# nano_bt_langsung.net
KiCad netlist of a schematic drawn in EAGLE
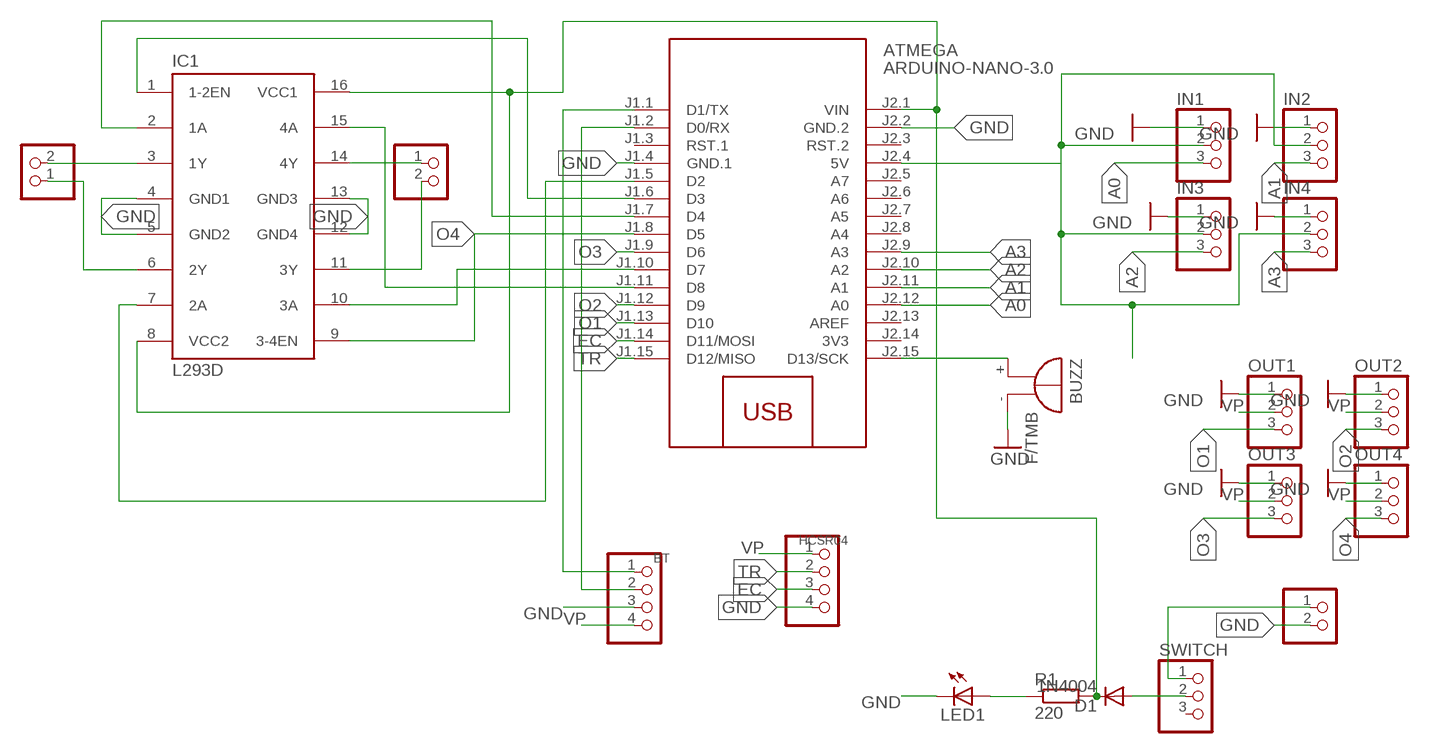
[diagram p0: schematic, sheet 1]

(export (version "E")
  (design (tool "Eeschema 10.0.6"))
  (components
    (comp (ref "ATMEGA")
      (value "ARDUINO-NANO-3.0")
      (footprint "eagle-import:ARDUINO-NANO-3.0")
      (libsource (lib "eagle-import") (part "ARDUINO-NANO-3.0"))
    )
    (comp (ref "BT")
      (value "PINHD-1X4")
      (footprint "eagle-import:1X04")
      (libsource (lib "eagle-import") (part "PINHD-1X4"))
    )
    (comp (ref "BUZZ")
      (value "F/TMB")
      (footprint "eagle-import:F_TMB")
      (libsource (lib "eagle-import") (part "F/TMB"))
    )
    (comp (ref "D1")
      (value "1N4004")
      (footprint "eagle-import:DO41-10")
      (libsource (lib "eagle-import") (part "1N4004"))
    )
    (comp (ref "DCV")
      (value "PINHD-1X2")
      (footprint "eagle-import:1X02")
      (libsource (lib "eagle-import") (part "PINHD-1X2"))
    )
    (comp (ref "HCSR04")
      (value "PINHD-1X4")
      (footprint "eagle-import:1X04")
      (libsource (lib "eagle-import") (part "PINHD-1X4"))
    )
    (comp (ref "IC1")
      (value "L293D")
      (footprint "eagle-import:DIL16")
      (libsource (lib "eagle-import") (part "L293D"))
    )
    (comp (ref "IN1")
      (value "PINHD-1X3")
      (footprint "eagle-import:1X03")
      (libsource (lib "eagle-import") (part "PINHD-1X3"))
    )
    (comp (ref "IN2")
      (value "PINHD-1X3")
      (footprint "eagle-import:1X03")
      (libsource (lib "eagle-import") (part "PINHD-1X3"))
    )
    (comp (ref "IN3")
      (value "PINHD-1X3")
      (footprint "eagle-import:1X03")
      (libsource (lib "eagle-import") (part "PINHD-1X3"))
    )
    (comp (ref "IN4")
      (value "PINHD-1X3")
      (footprint "eagle-import:1X03")
      (libsource (lib "eagle-import") (part "PINHD-1X3"))
    )
    (comp (ref "LED1")
      (value "LED3MM")
      (footprint "eagle-import:LED3MM")
      (libsource (lib "eagle-import") (part "LED3MM"))
    )
    (comp (ref "MT1")
      (value "PINHD-1X2")
      (footprint "eagle-import:1X02")
      (libsource (lib "eagle-import") (part "PINHD-1X2"))
    )
    (comp (ref "MT2")
      (value "PINHD-1X2")
      (footprint "eagle-import:1X02")
      (libsource (lib "eagle-import") (part "PINHD-1X2"))
    )
    (comp (ref "OUT1")
      (value "PINHD-1X3")
      (footprint "eagle-import:1X03")
      (libsource (lib "eagle-import") (part "PINHD-1X3"))
    )
    (comp (ref "OUT2")
      (value "PINHD-1X3")
      (footprint "eagle-import:1X03")
      (libsource (lib "eagle-import") (part "PINHD-1X3"))
    )
    (comp (ref "OUT3")
      (value "PINHD-1X3")
      (footprint "eagle-import:1X03")
      (libsource (lib "eagle-import") (part "PINHD-1X3"))
    )
    (comp (ref "OUT4")
      (value "PINHD-1X3")
      (footprint "eagle-import:1X03")
      (libsource (lib "eagle-import") (part "PINHD-1X3"))
    )
    (comp (ref "R1")
      (value "220")
      (footprint "eagle-import:0204_7")
      (libsource (lib "eagle-import") (part "R-EU_0204/7"))
    )
    (comp (ref "SWITCH")
      (value "PINHD-1X3")
      (footprint "eagle-import:1X03")
      (libsource (lib "eagle-import") (part "adafruit_arduino_PINHD-1X3"))
    )
  )
  (nets
    (net (code "1") (name "/3V3") (class "Default")
      (node (ref "ATMEGA") (pin "J2.14") (pinfunction "3V3_J2.14") (pintype "power_in"))
    )
    (net (code "2") (name "/VP") (class "Default")
      (node (ref "ATMEGA") (pin "J2.4") (pinfunction "5V_J2.4") (pintype "power_in"))
      (node (ref "BT") (pin "4") (pinfunction "4_4") (pintype "passive"))
      (node (ref "HCSR04") (pin "1") (pinfunction "1_1") (pintype "passive"))
      (node (ref "IN1") (pin "2") (pinfunction "2_2") (pintype "passive"))
      (node (ref "IN2") (pin "2") (pinfunction "2_2") (pintype "passive"))
      (node (ref "IN3") (pin "2") (pinfunction "2_2") (pintype "passive"))
      (node (ref "IN4") (pin "2") (pinfunction "2_2") (pintype "passive"))
      (node (ref "OUT1") (pin "2") (pinfunction "2_2") (pintype "passive"))
      (node (ref "OUT2") (pin "2") (pinfunction "2_2") (pintype "passive"))
      (node (ref "OUT3") (pin "2") (pinfunction "2_2") (pintype "passive"))
      (node (ref "OUT4") (pin "2") (pinfunction "2_2") (pintype "passive"))
    )
    (net (code "3") (name "A0") (class "Default")
      (node (ref "ATMEGA") (pin "J2.12") (pinfunction "A0_J2.12") (pintype "bidirectional"))
      (node (ref "IN1") (pin "3") (pinfunction "3_3") (pintype "passive"))
    )
    (net (code "4") (name "A1") (class "Default")
      (node (ref "ATMEGA") (pin "J2.11") (pinfunction "A1_J2.11") (pintype "bidirectional"))
      (node (ref "IN2") (pin "3") (pinfunction "3_3") (pintype "passive"))
    )
    (net (code "5") (name "A2") (class "Default")
      (node (ref "ATMEGA") (pin "J2.10") (pinfunction "A2_J2.10") (pintype "bidirectional"))
      (node (ref "IN3") (pin "3") (pinfunction "3_3") (pintype "passive"))
    )
    (net (code "6") (name "A3") (class "Default")
      (node (ref "ATMEGA") (pin "J2.9") (pinfunction "A3_J2.9") (pintype "bidirectional"))
      (node (ref "IN4") (pin "3") (pinfunction "3_3") (pintype "passive"))
    )
    (net (code "7") (name "EC") (class "Default")
      (node (ref "ATMEGA") (pin "J1.14") (pinfunction "D11/MOSI_J1.14") (pintype "bidirectional"))
      (node (ref "HCSR04") (pin "3") (pinfunction "3_3") (pintype "passive"))
    )
    (net (code "8") (name "GND") (class "Default")
      (node (ref "ATMEGA") (pin "J1.4") (pinfunction "GND.1_J1.4") (pintype "power_in"))
      (node (ref "ATMEGA") (pin "J2.2") (pinfunction "GND.2_J2.2") (pintype "power_in"))
      (node (ref "BT") (pin "3") (pinfunction "3_3") (pintype "passive"))
      (node (ref "BUZZ") (pin "-") (pinfunction "-_-") (pintype "passive"))
      (node (ref "DCV") (pin "2") (pinfunction "2_2") (pintype "passive"))
      (node (ref "HCSR04") (pin "4") (pinfunction "4_4") (pintype "passive"))
      (node (ref "IC1") (pin "12") (pinfunction "GND4_12") (pintype "power_in"))
      (node (ref "IC1") (pin "13") (pinfunction "GND3_13") (pintype "power_in"))
      (node (ref "IC1") (pin "4") (pinfunction "GND1_4") (pintype "power_in"))
      (node (ref "IC1") (pin "5") (pinfunction "GND2_5") (pintype "power_in"))
      (node (ref "IN1") (pin "1") (pinfunction "1_1") (pintype "passive"))
      (node (ref "IN2") (pin "1") (pinfunction "1_1") (pintype "passive"))
      (node (ref "IN3") (pin "1") (pinfunction "1_1") (pintype "passive"))
      (node (ref "IN4") (pin "1") (pinfunction "1_1") (pintype "passive"))
      (node (ref "LED1") (pin "K") (pinfunction "C_K") (pintype "passive"))
      (node (ref "OUT1") (pin "1") (pinfunction "1_1") (pintype "passive"))
      (node (ref "OUT2") (pin "1") (pinfunction "1_1") (pintype "passive"))
      (node (ref "OUT3") (pin "1") (pinfunction "1_1") (pintype "passive"))
      (node (ref "OUT4") (pin "1") (pinfunction "1_1") (pintype "passive"))
    )
    (net (code "9") (name "Net-(ATMEGA-D0{slash}RX)") (class "Default")
      (node (ref "ATMEGA") (pin "J1.2") (pinfunction "D0/RX_J1.2") (pintype "bidirectional"))
      (node (ref "BT") (pin "2") (pinfunction "2_2") (pintype "passive"))
    )
    (net (code "10") (name "Net-(ATMEGA-D1{slash}TX)") (class "Default")
      (node (ref "ATMEGA") (pin "J1.1") (pinfunction "D1/TX_J1.1") (pintype "bidirectional"))
      (node (ref "BT") (pin "1") (pinfunction "1_1") (pintype "passive"))
    )
    (net (code "11") (name "Net-(ATMEGA-D2)") (class "Default")
      (node (ref "ATMEGA") (pin "J1.5") (pinfunction "D2_J1.5") (pintype "bidirectional"))
      (node (ref "IC1") (pin "7") (pinfunction "2A_7") (pintype "input"))
    )
    (net (code "12") (name "Net-(ATMEGA-D3)") (class "Default")
      (node (ref "ATMEGA") (pin "J1.6") (pinfunction "D3_J1.6") (pintype "bidirectional"))
      (node (ref "IC1") (pin "1") (pinfunction "1-2EN_1") (pintype "input"))
    )
    (net (code "13") (name "Net-(ATMEGA-D4)") (class "Default")
      (node (ref "ATMEGA") (pin "J1.7") (pinfunction "D4_J1.7") (pintype "bidirectional"))
      (node (ref "IC1") (pin "2") (pinfunction "1A_2") (pintype "input"))
    )
    (net (code "14") (name "Net-(ATMEGA-D7)") (class "Default")
      (node (ref "ATMEGA") (pin "J1.10") (pinfunction "D7_J1.10") (pintype "bidirectional"))
      (node (ref "IC1") (pin "10") (pinfunction "3A_10") (pintype "input"))
    )
    (net (code "15") (name "Net-(ATMEGA-D8)") (class "Default")
      (node (ref "ATMEGA") (pin "J1.11") (pinfunction "D8_J1.11") (pintype "bidirectional"))
      (node (ref "IC1") (pin "15") (pinfunction "4A_15") (pintype "input"))
    )
    (net (code "16") (name "Net-(ATMEGA-D13{slash}SCK)") (class "Default")
      (node (ref "ATMEGA") (pin "J2.15") (pinfunction "D13/SCK_J2.15") (pintype "bidirectional"))
      (node (ref "BUZZ") (pin "+") (pinfunction "+_+") (pintype "passive"))
    )
    (net (code "17") (name "Net-(ATMEGA-VIN)") (class "Default")
      (node (ref "ATMEGA") (pin "J2.1") (pinfunction "VIN_J2.1") (pintype "power_in"))
      (node (ref "D1") (pin "C") (pinfunction "C_C") (pintype "passive"))
      (node (ref "IC1") (pin "16") (pinfunction "VCC1_16") (pintype "power_in"))
      (node (ref "IC1") (pin "8") (pinfunction "VCC2_8") (pintype "power_in"))
      (node (ref "R1") (pin "2") (pinfunction "2_2") (pintype "passive"))
    )
    (net (code "18") (name "Net-(D1-PadA)") (class "Default")
      (node (ref "D1") (pin "A") (pinfunction "A_A") (pintype "passive"))
      (node (ref "SWITCH") (pin "2") (pinfunction "2_2") (pintype "passive"))
    )
    (net (code "19") (name "Net-(DCV-Pad1)") (class "Default")
      (node (ref "DCV") (pin "1") (pinfunction "1_1") (pintype "passive"))
      (node (ref "SWITCH") (pin "1") (pinfunction "1_1") (pintype "passive"))
    )
    (net (code "20") (name "Net-(IC1-1Y)") (class "Default")
      (node (ref "IC1") (pin "3") (pinfunction "1Y_3") (pintype "output"))
      (node (ref "MT1") (pin "2") (pinfunction "2_2") (pintype "passive"))
    )
    (net (code "21") (name "Net-(IC1-2Y)") (class "Default")
      (node (ref "IC1") (pin "6") (pinfunction "2Y_6") (pintype "output"))
      (node (ref "MT1") (pin "1") (pinfunction "1_1") (pintype "passive"))
    )
    (net (code "22") (name "Net-(IC1-3Y)") (class "Default")
      (node (ref "IC1") (pin "11") (pinfunction "3Y_11") (pintype "output"))
      (node (ref "MT2") (pin "2") (pinfunction "2_2") (pintype "passive"))
    )
    (net (code "23") (name "Net-(IC1-4Y)") (class "Default")
      (node (ref "IC1") (pin "14") (pinfunction "4Y_14") (pintype "output"))
      (node (ref "MT2") (pin "1") (pinfunction "1_1") (pintype "passive"))
    )
    (net (code "24") (name "Net-(LED1-PadA)") (class "Default")
      (node (ref "LED1") (pin "A") (pinfunction "A_A") (pintype "passive"))
      (node (ref "R1") (pin "1") (pinfunction "1_1") (pintype "passive"))
    )
    (net (code "25") (name "O1") (class "Default")
      (node (ref "ATMEGA") (pin "J1.13") (pinfunction "D10_J1.13") (pintype "bidirectional"))
      (node (ref "OUT1") (pin "3") (pinfunction "3_3") (pintype "passive"))
    )
    (net (code "26") (name "O2") (class "Default")
      (node (ref "ATMEGA") (pin "J1.12") (pinfunction "D9_J1.12") (pintype "bidirectional"))
      (node (ref "OUT2") (pin "3") (pinfunction "3_3") (pintype "passive"))
    )
    (net (code "27") (name "O3") (class "Default")
      (node (ref "ATMEGA") (pin "J1.9") (pinfunction "D6_J1.9") (pintype "bidirectional"))
      (node (ref "OUT3") (pin "3") (pinfunction "3_3") (pintype "passive"))
    )
    (net (code "28") (name "O4") (class "Default")
      (node (ref "ATMEGA") (pin "J1.8") (pinfunction "D5_J1.8") (pintype "bidirectional"))
      (node (ref "IC1") (pin "9") (pinfunction "3-4EN_9") (pintype "input"))
      (node (ref "OUT4") (pin "3") (pinfunction "3_3") (pintype "passive"))
    )
    (net (code "29") (name "TR") (class "Default")
      (node (ref "ATMEGA") (pin "J1.15") (pinfunction "D12/MISO_J1.15") (pintype "bidirectional"))
      (node (ref "HCSR04") (pin "2") (pinfunction "2_2") (pintype "passive"))
    )
    (net (code "30") (name "unconnected-(ATMEGA-A4-PadJ2.8)") (class "Default")
      (node (ref "ATMEGA") (pin "J2.8") (pinfunction "A4_J2.8") (pintype "bidirectional"))
    )
    (net (code "31") (name "unconnected-(ATMEGA-A5-PadJ2.7)") (class "Default")
      (node (ref "ATMEGA") (pin "J2.7") (pinfunction "A5_J2.7") (pintype "bidirectional"))
    )
    (net (code "32") (name "unconnected-(ATMEGA-A6-PadJ2.6)") (class "Default")
      (node (ref "ATMEGA") (pin "J2.6") (pinfunction "A6_J2.6") (pintype "bidirectional"))
    )
    (net (code "33") (name "unconnected-(ATMEGA-A7-PadJ2.5)") (class "Default")
      (node (ref "ATMEGA") (pin "J2.5") (pinfunction "A7_J2.5") (pintype "bidirectional"))
    )
    (net (code "34") (name "unconnected-(ATMEGA-AREF-PadJ2.13)") (class "Default")
      (node (ref "ATMEGA") (pin "J2.13") (pinfunction "AREF_J2.13") (pintype "bidirectional"))
    )
    (net (code "35") (name "unconnected-(ATMEGA-RST.1-PadJ1.3)") (class "Default")
      (node (ref "ATMEGA") (pin "J1.3") (pinfunction "RST.1_J1.3") (pintype "bidirectional"))
    )
    (net (code "36") (name "unconnected-(ATMEGA-RST.2-PadJ2.3)") (class "Default")
      (node (ref "ATMEGA") (pin "J2.3") (pinfunction "RST.2_J2.3") (pintype "bidirectional"))
    )
    (net (code "37") (name "unconnected-(SWITCH-Pad3)") (class "Default")
      (node (ref "SWITCH") (pin "3") (pinfunction "3_3") (pintype "passive"))
    )
  )
)
